# Steeringwheel_wired_remote_V2.net
KiCad netlist of a schematic drawn in EAGLE
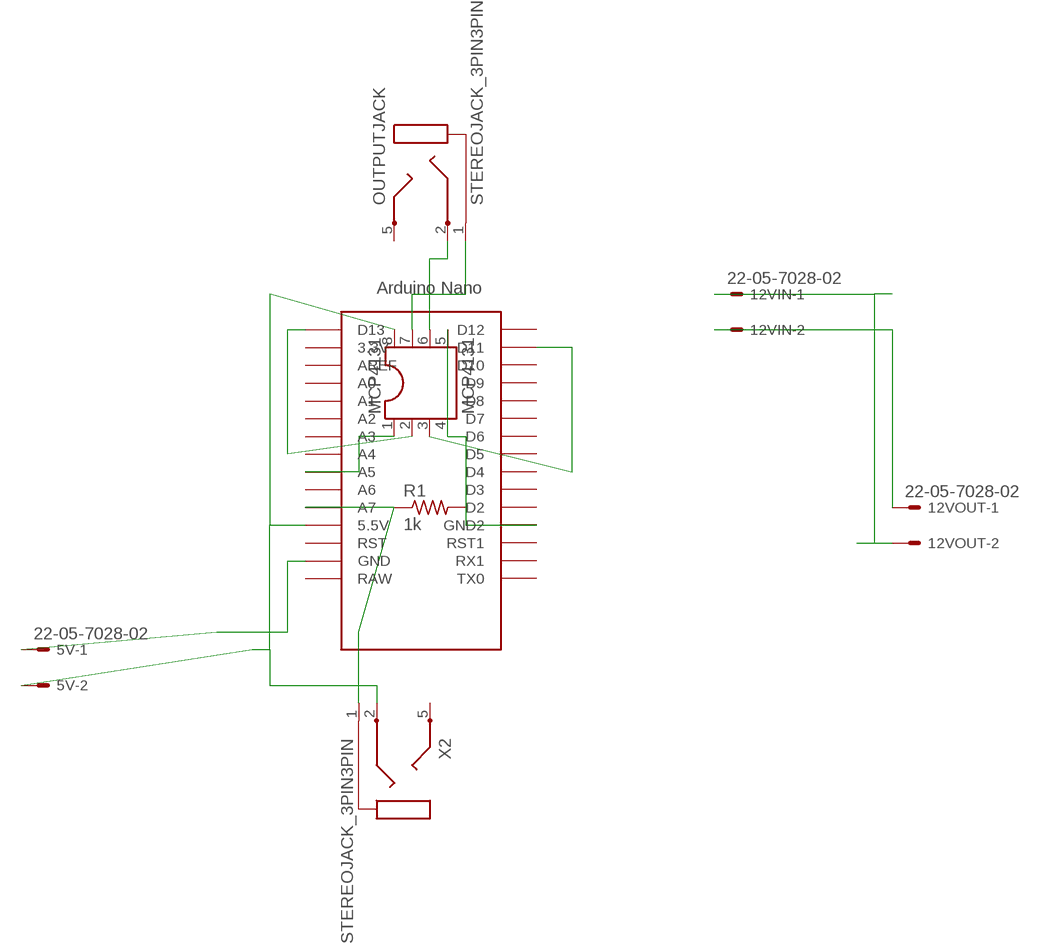
[diagram p0: schematic, sheet 1]

(export (version "E")
  (design (tool "Eeschema 10.0.6"))
  (components
    (comp (ref "5V")
      (value "22-05-7028-02")
      (footprint "eagle-import:7395-02")
      (libsource (lib "eagle-import") (part "22-?-0205-7028"))
    )
    (comp (ref "12VIN")
      (value "22-05-7028-02")
      (footprint "eagle-import:7395-02")
      (libsource (lib "eagle-import") (part "22-?-0205-7028"))
    )
    (comp (ref "12VOUT")
      (value "22-05-7028-02")
      (footprint "eagle-import:7395-02")
      (libsource (lib "eagle-import") (part "22-?-0205-7028"))
    )
    (comp (ref "IC1")
      (value "MCP4131")
      (footprint "eagle-import:DIL08")
      (libsource (lib "eagle-import") (part "DIL8"))
    )
    (comp (ref "OUTPUTJACK")
      (value "STEREOJACK_3PIN3PIN")
      (footprint "eagle-import:STX3000")
      (libsource (lib "eagle-import") (part "STEREOJACK_3PIN3PIN"))
    )
    (comp (ref "R1")
      (value "1k")
      (footprint "eagle-import:0204_5")
      (libsource (lib "eagle-import") (part "R-US_0204/5"))
    )
    (comp (ref "U$2")
      (value "NANO")
      (footprint "eagle-import:NANO_NOISPC")
      (libsource (lib "eagle-import") (part "NANO"))
    )
    (comp (ref "X2")
      (value "STEREOJACK_3PIN3PIN")
      (footprint "eagle-import:STX3000")
      (libsource (lib "eagle-import") (part "STEREOJACK_3PIN3PIN"))
    )
  )
  (nets
    (net (code "1") (name "/GND") (class "Default")
      (node (ref "5V") (pin "1") (pinfunction "S_1") (pintype "passive"))
      (node (ref "IC1") (pin "4") (pinfunction "GND_4") (pintype "passive"))
      (node (ref "IC1") (pin "5") (pinfunction "P0A_5") (pintype "passive"))
      (node (ref "R1") (pin "2") (pinfunction "2_2") (pintype "passive"))
      (node (ref "U$2") (pin "GND") (pinfunction "GND_GND") (pintype "bidirectional"))
      (node (ref "U$2") (pin "GND1") (pinfunction "GND2_GND1") (pintype "bidirectional"))
    )
    (net (code "2") (name "Net-(5VB-S)") (class "Default")
      (node (ref "5V") (pin "2") (pinfunction "S_2") (pintype "passive"))
      (node (ref "IC1") (pin "8") (pinfunction "VCC_8") (pintype "passive"))
      (node (ref "U$2") (pin "5V") (pinfunction "5.5V_5V") (pintype "bidirectional"))
      (node (ref "X2") (pin "2") (pinfunction "2_2") (pintype "passive"))
    )
    (net (code "3") (name "Net-(12VINA-S)") (class "Default")
      (node (ref "12VIN") (pin "1") (pinfunction "S_1") (pintype "passive"))
      (node (ref "12VOUT") (pin "2") (pinfunction "S_2") (pintype "passive"))
    )
    (net (code "4") (name "Net-(12VINB-S)") (class "Default")
      (node (ref "12VIN") (pin "2") (pinfunction "S_2") (pintype "passive"))
      (node (ref "12VOUT") (pin "1") (pinfunction "S_1") (pintype "passive"))
    )
    (net (code "5") (name "Net-(IC1-P0B)") (class "Default")
      (node (ref "IC1") (pin "7") (pinfunction "P0B_7") (pintype "passive"))
      (node (ref "OUTPUTJACK") (pin "1") (pinfunction "1_1") (pintype "passive"))
    )
    (net (code "6") (name "Net-(IC1-P0W)") (class "Default")
      (node (ref "IC1") (pin "6") (pinfunction "P0W_6") (pintype "passive"))
      (node (ref "OUTPUTJACK") (pin "2") (pinfunction "2_2") (pintype "passive"))
    )
    (net (code "7") (name "Net-(IC1-SCK)") (class "Default")
      (node (ref "IC1") (pin "2") (pinfunction "SCK_2") (pintype "passive"))
      (node (ref "U$2") (pin "D13") (pinfunction "D13_D13") (pintype "bidirectional"))
    )
    (net (code "8") (name "Net-(IC1-SDI)") (class "Default")
      (node (ref "IC1") (pin "3") (pinfunction "SDI_3") (pintype "passive"))
      (node (ref "U$2") (pin "D11") (pinfunction "D11_D11") (pintype "bidirectional"))
    )
    (net (code "9") (name "Net-(IC1-~{CS})") (class "Default")
      (node (ref "IC1") (pin "1") (pinfunction "~{CS}_1") (pintype "passive"))
      (node (ref "U$2") (pin "A5") (pinfunction "A5_A5") (pintype "bidirectional"))
    )
    (net (code "10") (name "Net-(R1-Pad1)") (class "Default")
      (node (ref "R1") (pin "1") (pinfunction "1_1") (pintype "passive"))
      (node (ref "U$2") (pin "A7") (pinfunction "A7_A7") (pintype "bidirectional"))
      (node (ref "X2") (pin "1") (pinfunction "1_1") (pintype "passive"))
    )
    (net (code "11") (name "unconnected-(OUTPUTJACK-Pad5)") (class "Default")
      (node (ref "OUTPUTJACK") (pin "5") (pinfunction "5_5") (pintype "passive"))
    )
    (net (code "12") (name "unconnected-(U$2-Pad3.3V)") (class "Default")
      (node (ref "U$2") (pin "3.3V") (pinfunction "3.3V_3.3V") (pintype "bidirectional"))
    )
    (net (code "13") (name "unconnected-(U$2-PadA0)") (class "Default")
      (node (ref "U$2") (pin "A0") (pinfunction "A0_A0") (pintype "bidirectional"))
    )
    (net (code "14") (name "unconnected-(U$2-PadA1)") (class "Default")
      (node (ref "U$2") (pin "A1") (pinfunction "A1_A1") (pintype "bidirectional"))
    )
    (net (code "15") (name "unconnected-(U$2-PadA2)") (class "Default")
      (node (ref "U$2") (pin "A2") (pinfunction "A2_A2") (pintype "bidirectional"))
    )
    (net (code "16") (name "unconnected-(U$2-PadA3)") (class "Default")
      (node (ref "U$2") (pin "A3") (pinfunction "A3_A3") (pintype "bidirectional"))
    )
    (net (code "17") (name "unconnected-(U$2-PadA4)") (class "Default")
      (node (ref "U$2") (pin "A4") (pinfunction "A4_A4") (pintype "bidirectional"))
    )
    (net (code "18") (name "unconnected-(U$2-PadA6)") (class "Default")
      (node (ref "U$2") (pin "A6") (pinfunction "A6_A6") (pintype "bidirectional"))
    )
    (net (code "19") (name "unconnected-(U$2-PadAREF)") (class "Default")
      (node (ref "U$2") (pin "AREF") (pinfunction "AREF_AREF") (pintype "bidirectional"))
    )
    (net (code "20") (name "unconnected-(U$2-PadD2)") (class "Default")
      (node (ref "U$2") (pin "D2") (pinfunction "D2_D2") (pintype "bidirectional"))
    )
    (net (code "21") (name "unconnected-(U$2-PadD3)") (class "Default")
      (node (ref "U$2") (pin "D3") (pinfunction "D3_D3") (pintype "bidirectional"))
    )
    (net (code "22") (name "unconnected-(U$2-PadD4)") (class "Default")
      (node (ref "U$2") (pin "D4") (pinfunction "D4_D4") (pintype "bidirectional"))
    )
    (net (code "23") (name "unconnected-(U$2-PadD5)") (class "Default")
      (node (ref "U$2") (pin "D5") (pinfunction "D5_D5") (pintype "bidirectional"))
    )
    (net (code "24") (name "unconnected-(U$2-PadD6)") (class "Default")
      (node (ref "U$2") (pin "D6") (pinfunction "D6_D6") (pintype "bidirectional"))
    )
    (net (code "25") (name "unconnected-(U$2-PadD7)") (class "Default")
      (node (ref "U$2") (pin "D7") (pinfunction "D7_D7") (pintype "bidirectional"))
    )
    (net (code "26") (name "unconnected-(U$2-PadD8)") (class "Default")
      (node (ref "U$2") (pin "D8") (pinfunction "D8_D8") (pintype "bidirectional"))
    )
    (net (code "27") (name "unconnected-(U$2-PadD9)") (class "Default")
      (node (ref "U$2") (pin "D9") (pinfunction "D9_D9") (pintype "bidirectional"))
    )
    (net (code "28") (name "unconnected-(U$2-PadD10)") (class "Default")
      (node (ref "U$2") (pin "D10") (pinfunction "D10_D10") (pintype "bidirectional"))
    )
    (net (code "29") (name "unconnected-(U$2-PadD12)") (class "Default")
      (node (ref "U$2") (pin "D12") (pinfunction "D12_D12") (pintype "bidirectional"))
    )
    (net (code "30") (name "unconnected-(U$2-PadRAW)") (class "Default")
      (node (ref "U$2") (pin "RAW") (pinfunction "RAW_RAW") (pintype "bidirectional"))
    )
    (net (code "31") (name "unconnected-(U$2-PadRST)") (class "Default")
      (node (ref "U$2") (pin "RST") (pinfunction "RST_RST") (pintype "bidirectional"))
    )
    (net (code "32") (name "unconnected-(U$2-PadRST1)") (class "Default")
      (node (ref "U$2") (pin "RST1") (pinfunction "RST1_RST1") (pintype "bidirectional"))
    )
    (net (code "33") (name "unconnected-(U$2-PadRX1)") (class "Default")
      (node (ref "U$2") (pin "RX1") (pinfunction "RX1_RX1") (pintype "bidirectional"))
    )
    (net (code "34") (name "unconnected-(U$2-PadTX0)") (class "Default")
      (node (ref "U$2") (pin "TX0") (pinfunction "TX0_TX0") (pintype "bidirectional"))
    )
    (net (code "35") (name "unconnected-(X2-Pad5)") (class "Default")
      (node (ref "X2") (pin "5") (pinfunction "5_5") (pintype "passive"))
    )
  )
)
